# Hdmi.net
KiCad netlist of a schematic drawn in Altium Designer
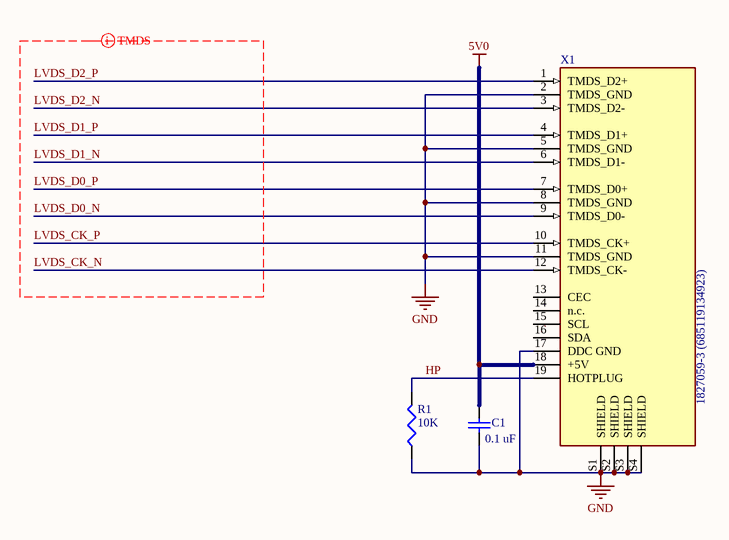
[diagram p0: Hdmi.SchDoc]

(export (version "E")
  (design (tool "Eeschema 10.0.6"))
  (components
    (comp (ref "C1")
      (value "0.1 uF")
      (footprint "0805 chip cap")
      (description "Capacitor")
      (libsource (lib "Schlib") (part "Cap"))
    )
    (comp (ref "R1")
      (value "10K")
      (footprint "0805 CHIP RES")
      (description "Resistor")
      (libsource (lib "Schlib") (part "CHIP RES"))
    )
    (comp (ref "X1")
      (value "1827059-3 (685119134923)")
      (footprint "1827059-3 (685119134923)")
      (fields (field (name "MP") "SS-53000-001") (field (name "MF") "Stewart Connector"))
      (libsource (lib "Schlib") (part "1827059-3 (685119134923)"))
    )
  )
  (nets
    (net (code "1") (name "/HP") (class "Default")
      (node (ref "R1") (pin "2") (pinfunction "2_2") (pintype "passive"))
      (node (ref "X1") (pin "19") (pinfunction "HOTPLUG_19") (pintype "passive"))
    )
    (net (code "2") (name "/LVDS_CK_N") (class "Default")
      (node (ref "X1") (pin "12") (pinfunction "TMDS_CK-_12") (pintype "input"))
    )
    (net (code "3") (name "/LVDS_CK_P") (class "Default")
      (node (ref "X1") (pin "10") (pinfunction "TMDS_CK+_10") (pintype "input"))
    )
    (net (code "4") (name "/LVDS_D0_N") (class "Default")
      (node (ref "X1") (pin "9") (pinfunction "TMDS_D0-_9") (pintype "input"))
    )
    (net (code "5") (name "/LVDS_D0_P") (class "Default")
      (node (ref "X1") (pin "7") (pinfunction "TMDS_D0+_7") (pintype "input"))
    )
    (net (code "6") (name "/LVDS_D1_N") (class "Default")
      (node (ref "X1") (pin "6") (pinfunction "TMDS_D1-_6") (pintype "input"))
    )
    (net (code "7") (name "/LVDS_D1_P") (class "Default")
      (node (ref "X1") (pin "4") (pinfunction "TMDS_D1+_4") (pintype "input"))
    )
    (net (code "8") (name "/LVDS_D2_N") (class "Default")
      (node (ref "X1") (pin "3") (pinfunction "TMDS_D2-_3") (pintype "input"))
    )
    (net (code "9") (name "/LVDS_D2_P") (class "Default")
      (node (ref "X1") (pin "1") (pinfunction "TMDS_D2+_1") (pintype "input"))
    )
    (net (code "10") (name "5V0") (class "Default")
      (node (ref "C1") (pin "2") (pinfunction "2_2") (pintype "passive"))
      (node (ref "X1") (pin "18") (pinfunction "+5V_18") (pintype "passive"))
    )
    (net (code "11") (name "GND") (class "Default")
      (node (ref "C1") (pin "1") (pinfunction "1_1") (pintype "passive"))
      (node (ref "R1") (pin "1") (pinfunction "1_1") (pintype "passive"))
      (node (ref "X1") (pin "11") (pinfunction "TMDS_GND_11") (pintype "power_in"))
      (node (ref "X1") (pin "17") (pinfunction "DDC_GND_17") (pintype "passive"))
      (node (ref "X1") (pin "2") (pinfunction "TMDS_GND_2") (pintype "power_in"))
      (node (ref "X1") (pin "5") (pinfunction "TMDS_GND_5") (pintype "power_in"))
      (node (ref "X1") (pin "8") (pinfunction "TMDS_GND_8") (pintype "power_in"))
      (node (ref "X1") (pin "S1") (pinfunction "SHIELD_S1") (pintype "passive"))
      (node (ref "X1") (pin "S2") (pinfunction "SHIELD_S2") (pintype "passive"))
      (node (ref "X1") (pin "S3") (pinfunction "SHIELD_S3") (pintype "passive"))
      (node (ref "X1") (pin "S4") (pinfunction "SHIELD_S4") (pintype "passive"))
    )
    (net (code "12") (name "unconnected-(X1-CEC-Pad13)") (class "Default")
      (node (ref "X1") (pin "13") (pinfunction "CEC_13") (pintype "passive"))
    )
    (net (code "13") (name "unconnected-(X1-SCL-Pad15)") (class "Default")
      (node (ref "X1") (pin "15") (pinfunction "SCL_15") (pintype "passive"))
    )
    (net (code "14") (name "unconnected-(X1-SDA-Pad16)") (class "Default")
      (node (ref "X1") (pin "16") (pinfunction "SDA_16") (pintype "passive"))
    )
    (net (code "15") (name "unconnected-(X1-n.c.-Pad14)") (class "Default")
      (node (ref "X1") (pin "14") (pinfunction "n.c._14") (pintype "passive"))
    )
  )
)
